# MCU.net
KiCad netlist of a schematic drawn in Altium Designer
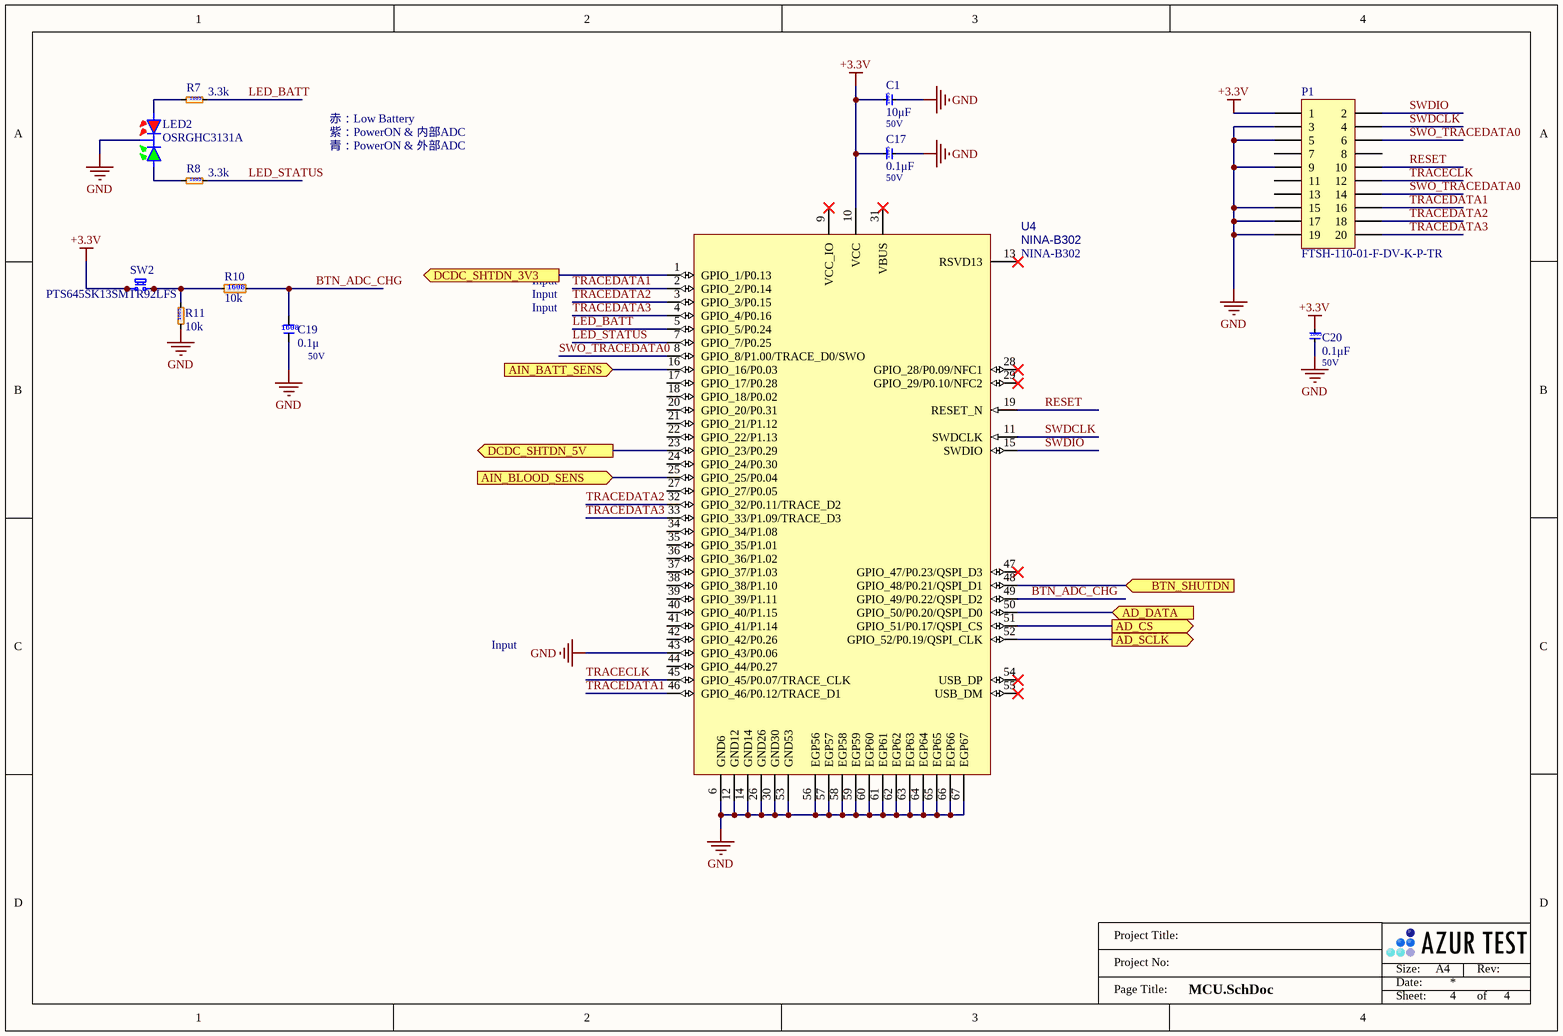
[diagram p0: MCU.SchDoc]

(export (version "E")
  (design (tool "Eeschema 10.0.6"))
  (components
    (comp (ref "C1")
      (value "GRM155F11H103Z")
      (footprint "C1005")
      (description "セラコン1005サイズ")
      (fields (field (name "TAG") "10μF") (field (name "VOLTAGE") "50V"))
      (libsource (lib "SSST") (part "C1005"))
    )
    (comp (ref "C17")
      (value "GRM1552C1H101J")
      (footprint "C1005")
      (description "セラコン1005サイズ")
      (fields (field (name "TAG") "0.1μF") (field (name "VOLTAGE") "50V"))
      (libsource (lib "SSST") (part "C1005"))
    )
    (comp (ref "C19")
      (value "GRM1885C1H101JA01D")
      (footprint "C1608")
      (description "セラコン1608サイズ")
      (fields (field (name "TAG") "0.1μ") (field (name "VOLTAGE") "50V"))
      (libsource (lib "Isoretion wear meater") (part "C1608"))
    )
    (comp (ref "C20")
      (value "GRM1552C1H101J")
      (footprint "C1005")
      (description "セラコン1005サイズ")
      (fields (field (name "TAG") "0.1μF") (field (name "VOLTAGE") "50V"))
      (libsource (lib "SSST") (part "C1005"))
    )
    (comp (ref "LED2")
      (value "OSRGHC3131A")
      (footprint "LED3COLORS")
      (description "2色LED（赤,青）")
      (libsource (lib "SSST") (part "OSRGHC3131A"))
    )
    (comp (ref "P1")
      (value "FTSH-110-01-F-DV-K-P-TR")
      (footprint "Headerpin 2x10")
      (description "Header, 2 x 10 -Pin 1.27mm")
      (libsource (lib "SSST") (part "FTSH-110-01-F-DV-K-P-TR"))
    )
    (comp (ref "R7")
      (value "RG1005P-332-B-T5")
      (footprint "R1005")
      (description "薄膜チップ抵抗1005サイズ")
      (fields (field (name "TAG") "3.3k"))
      (libsource (lib "") (part "MF1005_1"))
    )
    (comp (ref "R8")
      (value "RG1005P-332-B-T5")
      (footprint "R1005")
      (description "薄膜チップ抵抗1005サイズ")
      (fields (field (name "TAG") "3.3k"))
      (libsource (lib "") (part "MF1005_1"))
    )
    (comp (ref "R10")
      (value "RG1608P-103-B-T5")
      (footprint "R1608")
      (description "薄膜チップ抵抗1608サイズ")
      (fields (field (name "TAG") "10k"))
      (libsource (lib "SSST") (part "MF1608"))
    )
    (comp (ref "R11")
      (value "RG1005P-103-B-T5")
      (footprint "R1005")
      (description "薄膜チップ抵抗1005サイズ")
      (fields (field (name "TAG") "10k"))
      (libsource (lib "SSST") (part "MF1005"))
    )
    (comp (ref "SW2")
      (value "PTS645SK13SMTR92LFS")
      (footprint "PTS645SK13SMTR92LFS")
      (description "Tactile Switch 6 x 6mm")
      (libsource (lib "SSST") (part "PTS645SK13SMTR92LFS"))
    )
    (comp (ref "U4")
      (value "NINA-B302")
      (footprint "NINA_LGA67R_1500X1000X338_PIFA")
      (description "u-blox NINA-B302 Bluetooth 5 LE, 802.15.4 module")
      (fields (field (name "MANUFACTURER") "u-blox") (field (name "ALTIUM_VALUE") "NINA-B302"))
      (libsource (lib "SSST") (part "NINA-B302"))
    )
  )
  (nets
    (net (code "1") (name "+3.3V") (class "Default")
      (node (ref "C1") (pin "2") (pinfunction "2_2") (pintype "passive"))
      (node (ref "C17") (pin "2") (pinfunction "2_2") (pintype "passive"))
      (node (ref "C20") (pin "2") (pinfunction "2_2") (pintype "passive"))
      (node (ref "P1") (pin "1") (pinfunction "1_1") (pintype "passive"))
      (node (ref "SW2") (pin "1") (pinfunction "1_1") (pintype "passive"))
      (node (ref "SW2") (pin "2") (pinfunction "2_2") (pintype "passive"))
      (node (ref "U4") (pin "10") (pinfunction "VCC_10") (pintype "power_in"))
    )
    (net (code "2") (name "/AD_CS") (class "Default")
      (node (ref "U4") (pin "51") (pinfunction "GPIO_51/P0.17/QSPI_CS_51") (pintype "bidirectional"))
    )
    (net (code "3") (name "/AD_DATA") (class "Default")
      (node (ref "U4") (pin "50") (pinfunction "GPIO_50/P0.20/QSPI_D0_50") (pintype "bidirectional"))
    )
    (net (code "4") (name "/AD_SCLK") (class "Default")
      (node (ref "U4") (pin "52") (pinfunction "GPIO_52/P0.19/QSPI_CLK_52") (pintype "bidirectional"))
    )
    (net (code "5") (name "/AIN_BATT_SENS") (class "Default")
      (node (ref "U4") (pin "16") (pinfunction "GPIO_16/P0.03_16") (pintype "bidirectional"))
    )
    (net (code "6") (name "/AIN_BLOOD_SENS") (class "Default")
      (node (ref "U4") (pin "25") (pinfunction "GPIO_25/P0.04_25") (pintype "bidirectional"))
    )
    (net (code "7") (name "/BTN_ADC_CHG") (class "Default")
      (node (ref "C19") (pin "2") (pinfunction "2_2") (pintype "passive"))
      (node (ref "R10") (pin "2") (pinfunction "2_2") (pintype "passive"))
      (node (ref "U4") (pin "49") (pinfunction "GPIO_49/P0.22/QSPI_D2_49") (pintype "bidirectional"))
    )
    (net (code "8") (name "/BTN_SHUTDN") (class "Default")
      (node (ref "U4") (pin "48") (pinfunction "GPIO_48/P0.21/QSPI_D1_48") (pintype "bidirectional"))
    )
    (net (code "9") (name "/DCDC_SHTDN_3V3") (class "Default")
      (node (ref "U4") (pin "1") (pinfunction "GPIO_1/P0.13_1") (pintype "bidirectional"))
    )
    (net (code "10") (name "/DCDC_SHTDN_5V") (class "Default")
      (node (ref "U4") (pin "23") (pinfunction "GPIO_23/P0.29_23") (pintype "bidirectional"))
    )
    (net (code "11") (name "/LED_BATT") (class "Default")
      (node (ref "R7") (pin "2") (pinfunction "2_2") (pintype "passive"))
      (node (ref "U4") (pin "5") (pinfunction "GPIO_5/P0.24_5") (pintype "bidirectional"))
    )
    (net (code "12") (name "/LED_STATUS") (class "Default")
      (node (ref "R8") (pin "2") (pinfunction "2_2") (pintype "passive"))
      (node (ref "U4") (pin "7") (pinfunction "GPIO_7/P0.25_7") (pintype "bidirectional"))
    )
    (net (code "13") (name "/RESET") (class "Default")
      (node (ref "P1") (pin "10") (pinfunction "10_10") (pintype "passive"))
      (node (ref "U4") (pin "19") (pinfunction "RESET_N_19") (pintype "input"))
    )
    (net (code "14") (name "/SWDCLK") (class "Default")
      (node (ref "P1") (pin "4") (pinfunction "4_4") (pintype "passive"))
      (node (ref "U4") (pin "11") (pinfunction "SWDCLK_11") (pintype "input"))
    )
    (net (code "15") (name "/SWDIO") (class "Default")
      (node (ref "P1") (pin "2") (pinfunction "2_2") (pintype "passive"))
      (node (ref "U4") (pin "15") (pinfunction "SWDIO_15") (pintype "bidirectional"))
    )
    (net (code "16") (name "/SWO_TRACEDATA0") (class "Default")
      (node (ref "P1") (pin "14") (pinfunction "14_14") (pintype "passive"))
      (node (ref "P1") (pin "6") (pinfunction "6_6") (pintype "passive"))
      (node (ref "U4") (pin "8") (pinfunction "GPIO_8/P1.00/TRACE_D0/SWO_8") (pintype "bidirectional"))
    )
    (net (code "17") (name "/TRACECLK") (class "Default")
      (node (ref "P1") (pin "12") (pinfunction "12_12") (pintype "passive"))
      (node (ref "U4") (pin "45") (pinfunction "GPIO_45/P0.07/TRACE_CLK_45") (pintype "bidirectional"))
    )
    (net (code "18") (name "/TRACEDATA1") (class "Default")
      (node (ref "P1") (pin "16") (pinfunction "16_16") (pintype "passive"))
      (node (ref "U4") (pin "2") (pinfunction "GPIO_2/P0.14_2") (pintype "bidirectional"))
      (node (ref "U4") (pin "46") (pinfunction "GPIO_46/P0.12/TRACE_D1_46") (pintype "bidirectional"))
    )
    (net (code "19") (name "/TRACEDATA2") (class "Default")
      (node (ref "P1") (pin "18") (pinfunction "18_18") (pintype "passive"))
      (node (ref "U4") (pin "3") (pinfunction "GPIO_3/P0.15_3") (pintype "bidirectional"))
      (node (ref "U4") (pin "32") (pinfunction "GPIO_32/P0.11/TRACE_D2_32") (pintype "bidirectional"))
    )
    (net (code "20") (name "/TRACEDATA3") (class "Default")
      (node (ref "P1") (pin "20") (pinfunction "20_20") (pintype "passive"))
      (node (ref "U4") (pin "33") (pinfunction "GPIO_33/P1.09/TRACE_D3_33") (pintype "bidirectional"))
      (node (ref "U4") (pin "4") (pinfunction "GPIO_4/P0.16_4") (pintype "bidirectional"))
    )
    (net (code "21") (name "GND") (class "Default")
      (node (ref "C1") (pin "1") (pinfunction "1_1") (pintype "passive"))
      (node (ref "C17") (pin "1") (pinfunction "1_1") (pintype "passive"))
      (node (ref "C19") (pin "1") (pinfunction "1_1") (pintype "passive"))
      (node (ref "C20") (pin "1") (pinfunction "1_1") (pintype "passive"))
      (node (ref "LED2") (pin "2") (pinfunction "K_2") (pintype "passive"))
      (node (ref "P1") (pin "15") (pinfunction "15_15") (pintype "passive"))
      (node (ref "P1") (pin "17") (pinfunction "17_17") (pintype "passive"))
      (node (ref "P1") (pin "19") (pinfunction "19_19") (pintype "passive"))
      (node (ref "P1") (pin "3") (pinfunction "3_3") (pintype "passive"))
      (node (ref "P1") (pin "5") (pinfunction "5_5") (pintype "passive"))
      (node (ref "P1") (pin "9") (pinfunction "9_9") (pintype "passive"))
      (node (ref "R11") (pin "1") (pinfunction "1_1") (pintype "passive"))
      (node (ref "U4") (pin "12") (pinfunction "GND12_12") (pintype "power_in"))
      (node (ref "U4") (pin "14") (pinfunction "GND14_14") (pintype "power_in"))
      (node (ref "U4") (pin "26") (pinfunction "GND26_26") (pintype "power_in"))
      (node (ref "U4") (pin "30") (pinfunction "GND30_30") (pintype "power_in"))
      (node (ref "U4") (pin "43") (pinfunction "GPIO_43/P0.06_43") (pintype "bidirectional"))
      (node (ref "U4") (pin "53") (pinfunction "GND53_53") (pintype "power_in"))
      (node (ref "U4") (pin "56") (pinfunction "EGP56_56") (pintype "power_in"))
      (node (ref "U4") (pin "57") (pinfunction "EGP57_57") (pintype "power_in"))
      (node (ref "U4") (pin "58") (pinfunction "EGP58_58") (pintype "power_in"))
      (node (ref "U4") (pin "59") (pinfunction "EGP59_59") (pintype "power_in"))
      (node (ref "U4") (pin "6") (pinfunction "GND6_6") (pintype "power_in"))
      (node (ref "U4") (pin "60") (pinfunction "EGP60_60") (pintype "power_in"))
      (node (ref "U4") (pin "61") (pinfunction "EGP61_61") (pintype "power_in"))
      (node (ref "U4") (pin "62") (pinfunction "EGP62_62") (pintype "power_in"))
      (node (ref "U4") (pin "63") (pinfunction "EGP63_63") (pintype "power_in"))
      (node (ref "U4") (pin "64") (pinfunction "EGP64_64") (pintype "power_in"))
      (node (ref "U4") (pin "65") (pinfunction "EGP65_65") (pintype "power_in"))
      (node (ref "U4") (pin "66") (pinfunction "EGP66_66") (pintype "power_in"))
      (node (ref "U4") (pin "67") (pinfunction "EGP67_67") (pintype "power_in"))
    )
    (net (code "22") (name "Net-(LED2-A)") (class "Default")
      (node (ref "LED2") (pin "1") (pinfunction "A_1") (pintype "passive"))
      (node (ref "R8") (pin "1") (pinfunction "1_1") (pintype "passive"))
    )
    (net (code "23") (name "Net-(LED2-C)") (class "Default")
      (node (ref "LED2") (pin "3") (pinfunction "C_3") (pintype "passive"))
      (node (ref "R7") (pin "1") (pinfunction "1_1") (pintype "passive"))
    )
    (net (code "24") (name "Net-(R10-Pad1)") (class "Default")
      (node (ref "R10") (pin "1") (pinfunction "1_1") (pintype "passive"))
      (node (ref "R11") (pin "2") (pinfunction "2_2") (pintype "passive"))
      (node (ref "SW2") (pin "3") (pinfunction "3_3") (pintype "passive"))
      (node (ref "SW2") (pin "4") (pinfunction "4_4") (pintype "passive"))
    )
    (net (code "25") (name "unconnected-(P1-Pad7)") (class "Default")
      (node (ref "P1") (pin "7") (pinfunction "7_7") (pintype "passive"))
    )
    (net (code "26") (name "unconnected-(P1-Pad8)") (class "Default")
      (node (ref "P1") (pin "8") (pinfunction "8_8") (pintype "passive"))
    )
    (net (code "27") (name "unconnected-(P1-Pad11)") (class "Default")
      (node (ref "P1") (pin "11") (pinfunction "11_11") (pintype "passive"))
    )
    (net (code "28") (name "unconnected-(P1-Pad13)") (class "Default")
      (node (ref "P1") (pin "13") (pinfunction "13_13") (pintype "passive"))
    )
    (net (code "29") (name "unconnected-(U4-GPIO_17{slash}P0.28-Pad17)") (class "Default")
      (node (ref "U4") (pin "17") (pinfunction "GPIO_17/P0.28_17") (pintype "bidirectional"))
    )
    (net (code "30") (name "unconnected-(U4-GPIO_18{slash}P0.02-Pad18)") (class "Default")
      (node (ref "U4") (pin "18") (pinfunction "GPIO_18/P0.02_18") (pintype "bidirectional"))
    )
    (net (code "31") (name "unconnected-(U4-GPIO_20{slash}P0.31-Pad20)") (class "Default")
      (node (ref "U4") (pin "20") (pinfunction "GPIO_20/P0.31_20") (pintype "bidirectional"))
    )
    (net (code "32") (name "unconnected-(U4-GPIO_21{slash}P1.12-Pad21)") (class "Default")
      (node (ref "U4") (pin "21") (pinfunction "GPIO_21/P1.12_21") (pintype "bidirectional"))
    )
    (net (code "33") (name "unconnected-(U4-GPIO_22{slash}P1.13-Pad22)") (class "Default")
      (node (ref "U4") (pin "22") (pinfunction "GPIO_22/P1.13_22") (pintype "bidirectional"))
    )
    (net (code "34") (name "unconnected-(U4-GPIO_24{slash}P0.30-Pad24)") (class "Default")
      (node (ref "U4") (pin "24") (pinfunction "GPIO_24/P0.30_24") (pintype "bidirectional"))
    )
    (net (code "35") (name "unconnected-(U4-GPIO_27{slash}P0.05-Pad27)") (class "Default")
      (node (ref "U4") (pin "27") (pinfunction "GPIO_27/P0.05_27") (pintype "bidirectional"))
    )
    (net (code "36") (name "unconnected-(U4-GPIO_28{slash}P0.09{slash}NFC1-Pad28)") (class "Default")
      (node (ref "U4") (pin "28") (pinfunction "GPIO_28/P0.09/NFC1_28") (pintype "bidirectional+no_connect"))
    )
    (net (code "37") (name "unconnected-(U4-GPIO_29{slash}P0.10{slash}NFC2-Pad29)") (class "Default")
      (node (ref "U4") (pin "29") (pinfunction "GPIO_29/P0.10/NFC2_29") (pintype "bidirectional+no_connect"))
    )
    (net (code "38") (name "unconnected-(U4-GPIO_34{slash}P1.08-Pad34)") (class "Default")
      (node (ref "U4") (pin "34") (pinfunction "GPIO_34/P1.08_34") (pintype "bidirectional"))
    )
    (net (code "39") (name "unconnected-(U4-GPIO_35{slash}P1.01-Pad35)") (class "Default")
      (node (ref "U4") (pin "35") (pinfunction "GPIO_35/P1.01_35") (pintype "bidirectional"))
    )
    (net (code "40") (name "unconnected-(U4-GPIO_36{slash}P1.02-Pad36)") (class "Default")
      (node (ref "U4") (pin "36") (pinfunction "GPIO_36/P1.02_36") (pintype "bidirectional"))
    )
    (net (code "41") (name "unconnected-(U4-GPIO_37{slash}P1.03-Pad37)") (class "Default")
      (node (ref "U4") (pin "37") (pinfunction "GPIO_37/P1.03_37") (pintype "bidirectional"))
    )
    (net (code "42") (name "unconnected-(U4-GPIO_38{slash}P1.10-Pad38)") (class "Default")
      (node (ref "U4") (pin "38") (pinfunction "GPIO_38/P1.10_38") (pintype "bidirectional"))
    )
    (net (code "43") (name "unconnected-(U4-GPIO_39{slash}P1.11-Pad39)") (class "Default")
      (node (ref "U4") (pin "39") (pinfunction "GPIO_39/P1.11_39") (pintype "bidirectional"))
    )
    (net (code "44") (name "unconnected-(U4-GPIO_40{slash}P1.15-Pad40)") (class "Default")
      (node (ref "U4") (pin "40") (pinfunction "GPIO_40/P1.15_40") (pintype "bidirectional"))
    )
    (net (code "45") (name "unconnected-(U4-GPIO_41{slash}P1.14-Pad41)") (class "Default")
      (node (ref "U4") (pin "41") (pinfunction "GPIO_41/P1.14_41") (pintype "bidirectional"))
    )
    (net (code "46") (name "unconnected-(U4-GPIO_42{slash}P0.26-Pad42)") (class "Default")
      (node (ref "U4") (pin "42") (pinfunction "GPIO_42/P0.26_42") (pintype "bidirectional"))
    )
    (net (code "47") (name "unconnected-(U4-GPIO_44{slash}P0.27-Pad44)") (class "Default")
      (node (ref "U4") (pin "44") (pinfunction "GPIO_44/P0.27_44") (pintype "bidirectional"))
    )
    (net (code "48") (name "unconnected-(U4-GPIO_47{slash}P0.23{slash}QSPI_D3-Pad47)") (class "Default")
      (node (ref "U4") (pin "47") (pinfunction "GPIO_47/P0.23/QSPI_D3_47") (pintype "bidirectional+no_connect"))
    )
    (net (code "49") (name "unconnected-(U4-RSVD13-Pad13)") (class "Default")
      (node (ref "U4") (pin "13") (pinfunction "RSVD13_13") (pintype "passive+no_connect"))
    )
    (net (code "50") (name "unconnected-(U4-USB_DM-Pad55)") (class "Default")
      (node (ref "U4") (pin "55") (pinfunction "USB_DM_55") (pintype "bidirectional+no_connect"))
    )
    (net (code "51") (name "unconnected-(U4-USB_DP-Pad54)") (class "Default")
      (node (ref "U4") (pin "54") (pinfunction "USB_DP_54") (pintype "bidirectional+no_connect"))
    )
    (net (code "52") (name "unconnected-(U4-VBUS-Pad31)") (class "Default")
      (node (ref "U4") (pin "31") (pinfunction "VBUS_31") (pintype "power_in+no_connect"))
    )
    (net (code "53") (name "unconnected-(U4-VCC_IO-Pad9)") (class "Default")
      (node (ref "U4") (pin "9") (pinfunction "VCC_IO_9") (pintype "power_in+no_connect"))
    )
  )
)
